# FLOLED-BASE.net
KiCad netlist of a schematic drawn in Altium Designer
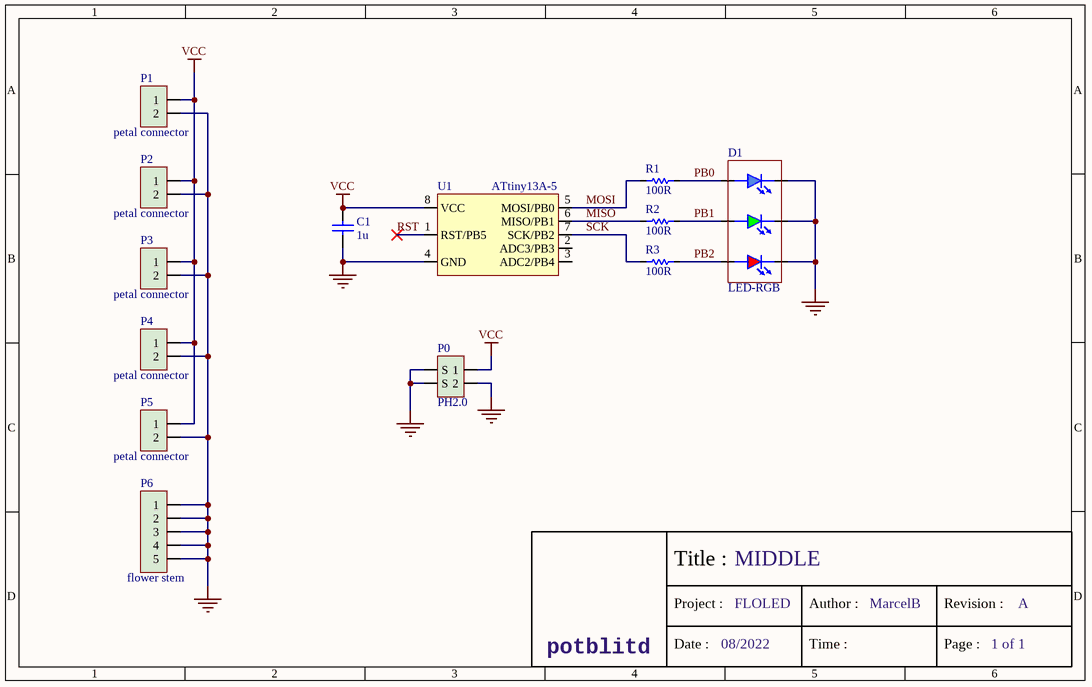
[diagram p0: FLOLED-BASE.SchDoc]

(export (version "E")
  (design (tool "Eeschema 10.0.6"))
  (components
    (comp (ref "C1")
      (value "Capacitor")
      (footprint "0603C")
      (description "Capacitor 1uF")
      (fields (field (name "ALTIUM_VALUE") "1u"))
      (libsource (lib "Simulation Generic Components") (part "Capacitor"))
    )
    (comp (ref "D1") (value "LED-RGB") (footprint "5050-RGB") (libsource (lib "AltiumLib") (part "LED-RGB")))
    (comp (ref "P0")
      (value "PH2.0")
      (footprint "2.0-2P LT")
      (description "PH2.0 SMD connector")
      (libsource (lib "AltiumLib") (part "PH2.0-2P-SMT"))
    )
    (comp (ref "P1")
      (value "petal connector")
      (footprint "FLOWER PETAL CONNECTORS")
      (description "Holes for flower petal PCB")
      (libsource (lib "AltiumLib") (part "2-pins Header"))
    )
    (comp (ref "P2")
      (value "petal connector")
      (footprint "FLOWER PETAL CONNECTORS")
      (description "Holes for flower petal PCB")
      (libsource (lib "AltiumLib") (part "2-pins Header"))
    )
    (comp (ref "P3")
      (value "petal connector")
      (footprint "FLOWER PETAL CONNECTORS")
      (description "Holes for flower petal PCB")
      (libsource (lib "AltiumLib") (part "2-pins Header"))
    )
    (comp (ref "P4")
      (value "petal connector")
      (footprint "FLOWER PETAL CONNECTORS")
      (description "Holes for flower petal PCB")
      (libsource (lib "AltiumLib") (part "2-pins Header"))
    )
    (comp (ref "P5")
      (value "petal connector")
      (footprint "FLOWER PETAL CONNECTORS")
      (description "Holes for flower petal PCB")
      (libsource (lib "AltiumLib") (part "2-pins Header"))
    )
    (comp (ref "P6")
      (value "flower stem")
      (footprint "FLOWER STEM")
      (description "Holes for flower stem rods")
      (libsource (lib "AltiumLib") (part "5-pins Header"))
    )
    (comp (ref "R1")
      (value "100R")
      (footprint "0805R")
      (description "Resistor 100Ω")
      (fields (field (name "Comment") "Resistor"))
      (libsource (lib "AltiumLib") (part "RES"))
    )
    (comp (ref "R2")
      (value "100R")
      (footprint "0805R")
      (description "Resistor 100Ω")
      (fields (field (name "Comment") "Resistor"))
      (libsource (lib "AltiumLib") (part "RES"))
    )
    (comp (ref "R3")
      (value "100R")
      (footprint "0805R")
      (description "Resistor 100Ω")
      (fields (field (name "Comment") "Resistor"))
      (libsource (lib "AltiumLib") (part "RES"))
    )
    (comp (ref "U1")
      (value "ATtiny13A-5")
      (footprint "DIP-8 - SMD")
      (description "tiny AVR 8-pin microcontroller")
      (libsource (lib "AltiumLib") (part "ATtiny13A-5"))
    )
  )
  (nets
    (net (code "1") (name "/MISO") (class "Default")
      (node (ref "R2") (pin "1") (pinfunction "1_1") (pintype "passive"))
      (node (ref "U1") (pin "6") (pinfunction "MISO/PB1_6") (pintype "passive"))
    )
    (net (code "2") (name "/MOSI") (class "Default")
      (node (ref "R1") (pin "1") (pinfunction "1_1") (pintype "passive"))
      (node (ref "U1") (pin "5") (pinfunction "MOSI/PB0_5") (pintype "passive"))
    )
    (net (code "3") (name "/PB0") (class "Default")
      (node (ref "D1") (pin "5") (pintype "passive"))
      (node (ref "R1") (pin "2") (pinfunction "2_2") (pintype "passive"))
    )
    (net (code "4") (name "/PB1") (class "Default")
      (node (ref "D1") (pin "3") (pintype "passive"))
      (node (ref "R2") (pin "2") (pinfunction "2_2") (pintype "passive"))
    )
    (net (code "5") (name "/PB2") (class "Default")
      (node (ref "D1") (pin "1") (pintype "passive"))
      (node (ref "R3") (pin "2") (pinfunction "2_2") (pintype "passive"))
    )
    (net (code "6") (name "/RST") (class "Default")
      (node (ref "U1") (pin "1") (pinfunction "RST/PB5_1") (pintype "passive+no_connect"))
    )
    (net (code "7") (name "/SCK") (class "Default")
      (node (ref "R3") (pin "1") (pinfunction "1_1") (pintype "passive"))
      (node (ref "U1") (pin "7") (pinfunction "SCK/PB2_7") (pintype "passive"))
    )
    (net (code "8") (name "GND") (class "Default")
      (node (ref "C1") (pin "1") (pinfunction "1_1") (pintype "passive"))
      (node (ref "D1") (pin "2") (pintype "passive"))
      (node (ref "D1") (pin "4") (pintype "passive"))
      (node (ref "D1") (pin "6") (pintype "passive"))
      (node (ref "P0") (pin "2") (pinfunction "2_2") (pintype "passive"))
      (node (ref "P0") (pin "3") (pinfunction "S_3") (pintype "passive"))
      (node (ref "P0") (pin "4") (pinfunction "S_4") (pintype "passive"))
      (node (ref "P1") (pin "2") (pinfunction "2_2") (pintype "passive"))
      (node (ref "P2") (pin "2") (pinfunction "2_2") (pintype "passive"))
      (node (ref "P3") (pin "2") (pinfunction "2_2") (pintype "passive"))
      (node (ref "P4") (pin "2") (pinfunction "2_2") (pintype "passive"))
      (node (ref "P5") (pin "2") (pinfunction "2_2") (pintype "passive"))
      (node (ref "P6") (pin "1") (pinfunction "1_1") (pintype "passive"))
      (node (ref "P6") (pin "2") (pinfunction "2_2") (pintype "passive"))
      (node (ref "P6") (pin "3") (pinfunction "3_3") (pintype "passive"))
      (node (ref "P6") (pin "4") (pinfunction "4_4") (pintype "passive"))
      (node (ref "P6") (pin "5") (pinfunction "5_5") (pintype "passive"))
      (node (ref "U1") (pin "4") (pinfunction "GND_4") (pintype "passive"))
    )
    (net (code "9") (name "VCC") (class "Default")
      (node (ref "C1") (pin "2") (pinfunction "2_2") (pintype "passive"))
      (node (ref "P0") (pin "1") (pinfunction "1_1") (pintype "passive"))
      (node (ref "P1") (pin "1") (pinfunction "1_1") (pintype "passive"))
      (node (ref "P2") (pin "1") (pinfunction "1_1") (pintype "passive"))
      (node (ref "P3") (pin "1") (pinfunction "1_1") (pintype "passive"))
      (node (ref "P4") (pin "1") (pinfunction "1_1") (pintype "passive"))
      (node (ref "P5") (pin "1") (pinfunction "1_1") (pintype "passive"))
      (node (ref "U1") (pin "8") (pinfunction "VCC_8") (pintype "passive"))
    )
    (net (code "10") (name "unconnected-(U1-ADC2{slash}PB4-Pad3)") (class "Default")
      (node (ref "U1") (pin "3") (pinfunction "ADC2/PB4_3") (pintype "passive"))
    )
    (net (code "11") (name "unconnected-(U1-ADC3{slash}PB3-Pad2)") (class "Default")
      (node (ref "U1") (pin "2") (pinfunction "ADC3/PB3_2") (pintype "passive"))
    )
  )
)
